# led2001-buck-flashlight-driver-17mm-mk-1.net
KiCad netlist of a schematic drawn in EAGLE
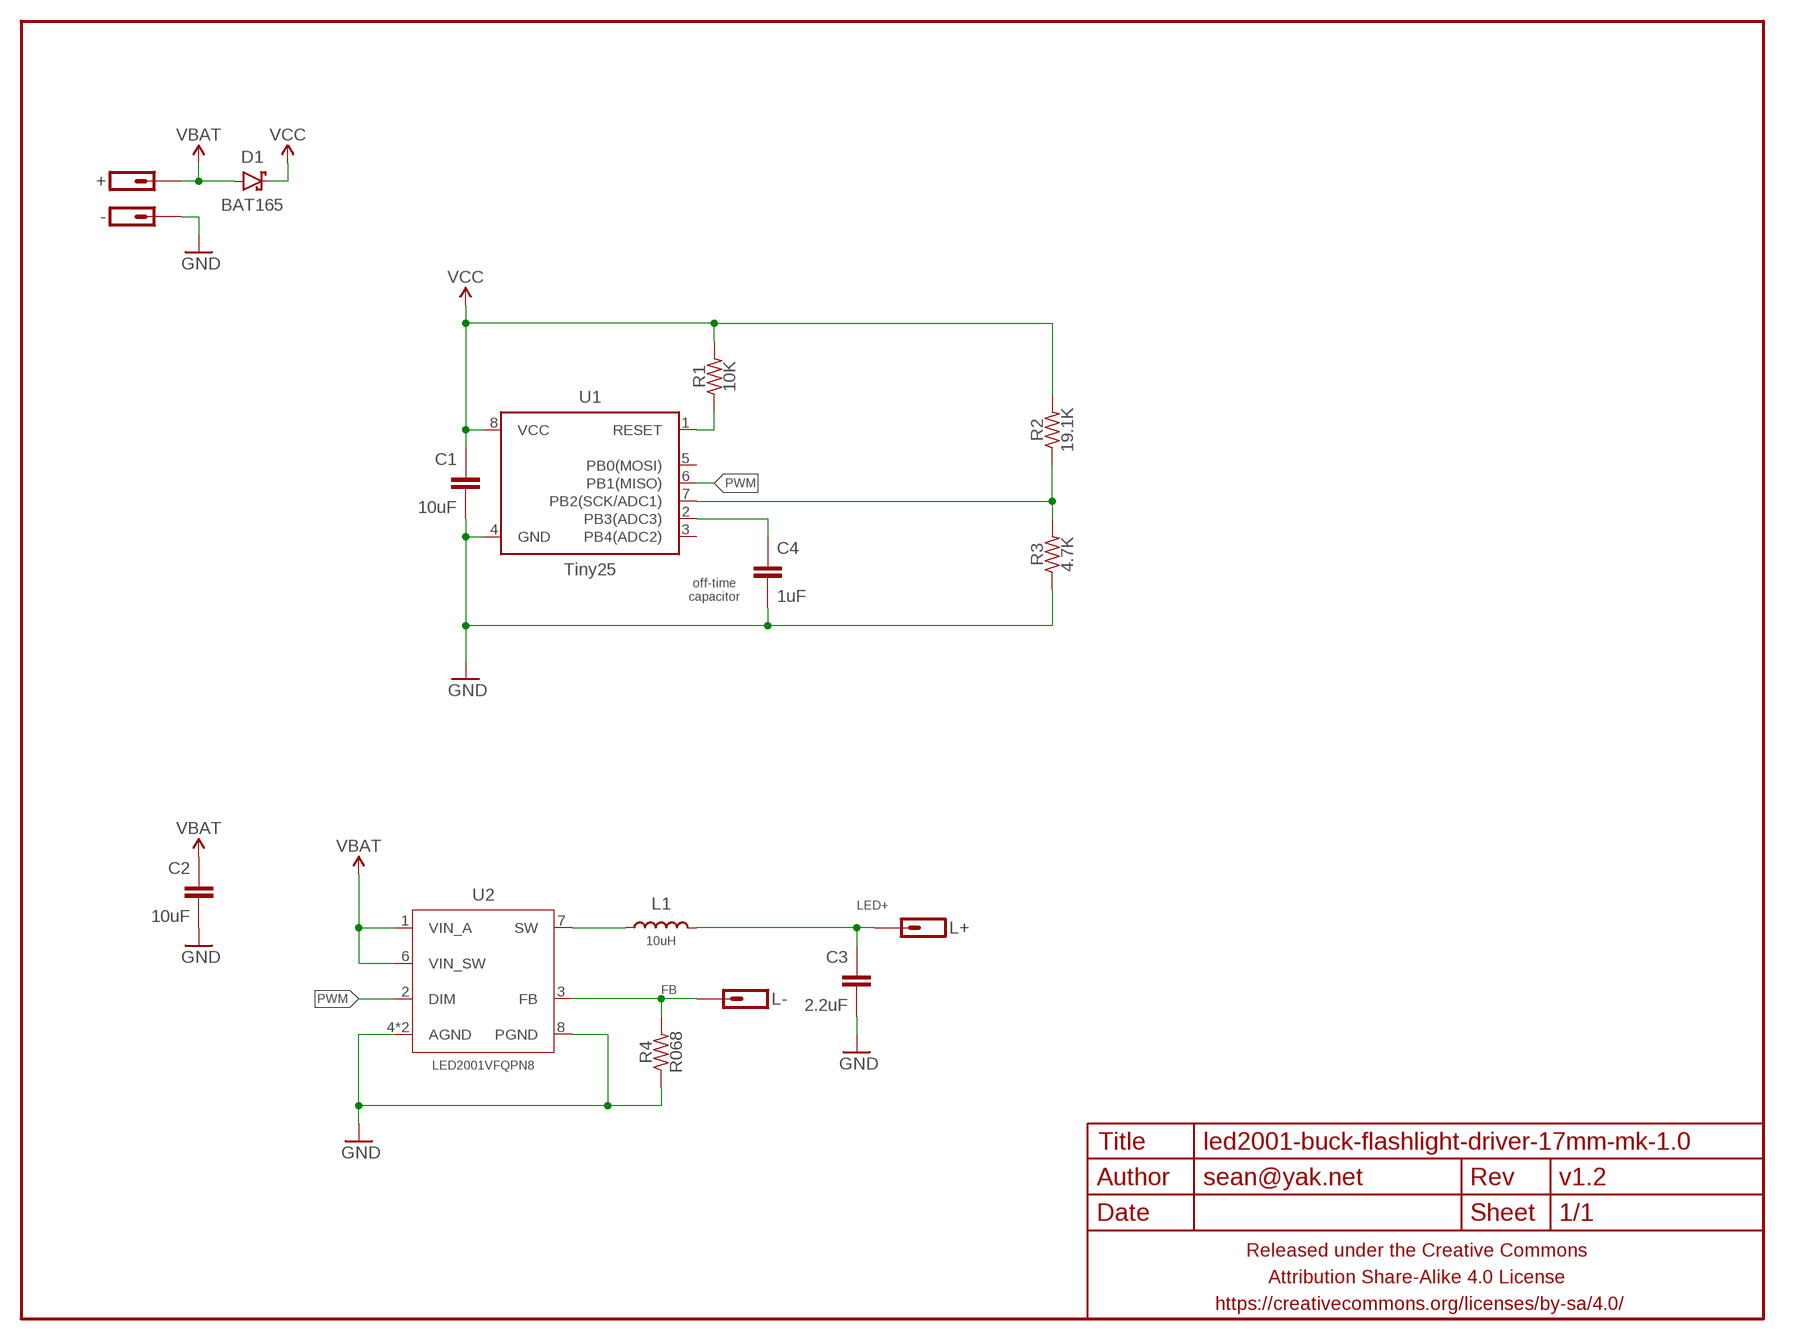
[diagram p0: schematic, sheet 1]

(export (version "E")
  (design (tool "Eeschema 10.0.6"))
  (components
    (comp (ref "+")
      (value "M01PTH-1MM-CIR-NS")
      (footprint "eagle-import:1X01-1MM-CIR-NS")
      (libsource (lib "eagle-import") (part "M01PTH-1MM-CIR-NS"))
    )
    (comp (ref "-")
      (value "M01NOT-A-VIA-NOPE")
      (footprint "eagle-import:1X01_NOSILK_NOSTOP")
      (libsource (lib "eagle-import") (part "M01NOT-A-VIA-NOPE"))
    )
    (comp (ref "C1")
      (value "10uF")
      (footprint "eagle-import:C0603-TIGHTER")
      (libsource (lib "eagle-import") (part "CAPACITOR-CERAMICC0603-TIGHTER"))
    )
    (comp (ref "C2")
      (value "10uF")
      (footprint "eagle-import:C0603-TIGHTER")
      (libsource (lib "eagle-import") (part "CAPACITOR-CERAMICC0603-TIGHTER"))
    )
    (comp (ref "C3")
      (value "2.2uF")
      (footprint "eagle-import:C0603-TIGHTER")
      (libsource (lib "eagle-import") (part "CAPACITOR-CERAMICC0603-TIGHTER"))
    )
    (comp (ref "C4")
      (value "1uF")
      (footprint "eagle-import:C0402")
      (libsource (lib "eagle-import") (part "CAPACITOR-CERAMICC0402"))
    )
    (comp (ref "D1")
      (value "BAT165")
      (footprint "eagle-import:SOD323-SCHOTTKY")
      (libsource (lib "eagle-import") (part "DIODE-SCHOTTKYSOD323"))
    )
    (comp (ref "FRAME1")
      (value "FRAME-LETTERNO_PACKAGE")
      (footprint "eagle-import:DUMMY")
      (fields (field (name "DESIGNER") "sean@yak.net") (field (name "VERSION") "v1.2"))
      (libsource (lib "eagle-import") (part "FRAME-LETTERNO_PACKAGE"))
    )
    (comp (ref "L+")
      (value "M01PTH-1MM-CIR-NS")
      (footprint "eagle-import:1X01-1MM-CIR-NS")
      (libsource (lib "eagle-import") (part "M01PTH-1MM-CIR-NS"))
    )
    (comp (ref "L-")
      (value "M01PTH-1MM-CIR-NS")
      (footprint "eagle-import:1X01-1MM-CIR-NS")
      (libsource (lib "eagle-import") (part "M01PTH-1MM-CIR-NS"))
    )
    (comp (ref "L1")
      (value "10uH")
      (footprint "eagle-import:XAL40X0")
      (libsource (lib "eagle-import") (part "INDUCTORXAL40X0"))
    )
    (comp (ref "R1")
      (value "10K")
      (footprint "eagle-import:R0402")
      (libsource (lib "eagle-import") (part "RESISTORR0402"))
    )
    (comp (ref "R2")
      (value "19.1K")
      (footprint "eagle-import:R0603-TIGHTER")
      (libsource (lib "eagle-import") (part "RESISTORR0603-TIGHTER"))
    )
    (comp (ref "R3")
      (value "4.7K")
      (footprint "eagle-import:R0603-TIGHTER")
      (libsource (lib "eagle-import") (part "RESISTORR0603-TIGHTER"))
    )
    (comp (ref "R4")
      (value "R068")
      (footprint "eagle-import:R0805-TIGHTER")
      (libsource (lib "eagle-import") (part "RESISTORR0805-TIGHTER"))
    )
    (comp (ref "U1")
      (value "Tiny25")
      (footprint "eagle-import:SO08-SKINNYPADS")
      (libsource (lib "eagle-import") (part "ATTINY45TINY25-SOICN-NARROWER"))
    )
    (comp (ref "U2")
      (value "LED2001VFQPN8")
      (footprint "eagle-import:VFQFPN8-4X4")
      (libsource (lib "eagle-import") (part "LED2001VFQPN8"))
    )
  )
  (nets
    (net (code "1") (name "/FB") (class "Default")
      (node (ref "L-") (pin "1") (pinfunction "1_1") (pintype "passive"))
      (node (ref "R4") (pin "2") (pinfunction "2_2") (pintype "passive"))
      (node (ref "U2") (pin "3") (pinfunction "FB_3") (pintype "bidirectional"))
    )
    (net (code "2") (name "/LED+") (class "Default")
      (node (ref "C3") (pin "1") (pinfunction "1_1") (pintype "passive"))
      (node (ref "L+") (pin "1") (pinfunction "1_1") (pintype "passive"))
      (node (ref "L1") (pin "P$2") (pinfunction "2_P$2") (pintype "passive"))
    )
    (net (code "3") (name "GND") (class "Default")
      (node (ref "-") (pin "P$1") (pinfunction "1_P$1") (pintype "passive"))
      (node (ref "C1") (pin "2") (pinfunction "2_2") (pintype "passive"))
      (node (ref "C2") (pin "2") (pinfunction "2_2") (pintype "passive"))
      (node (ref "C3") (pin "2") (pinfunction "2_2") (pintype "passive"))
      (node (ref "C4") (pin "2") (pinfunction "2_2") (pintype "passive"))
      (node (ref "R3") (pin "1") (pinfunction "1_1") (pintype "passive"))
      (node (ref "R4") (pin "1") (pinfunction "1_1") (pintype "passive"))
      (node (ref "U1") (pin "4") (pinfunction "GND_4") (pintype "bidirectional"))
      (node (ref "U2") (pin "4") (pinfunction "AGND_4") (pintype "bidirectional"))
      (node (ref "U2") (pin "8") (pinfunction "PGND_8") (pintype "bidirectional"))
      (node (ref "U2") (pin "9") (pinfunction "AGND_9") (pintype "bidirectional"))
    )
    (net (code "4") (name "Net-(L1-1)") (class "Default")
      (node (ref "L1") (pin "P$1") (pinfunction "1_P$1") (pintype "passive"))
      (node (ref "U2") (pin "7") (pinfunction "SW_7") (pintype "bidirectional"))
    )
    (net (code "5") (name "Net-(U1-PB2(SCK{slash}ADC1))") (class "Default")
      (node (ref "R2") (pin "1") (pinfunction "1_1") (pintype "passive"))
      (node (ref "R3") (pin "2") (pinfunction "2_2") (pintype "passive"))
      (node (ref "U1") (pin "7") (pinfunction "PB2(SCK/ADC1)_7") (pintype "bidirectional"))
    )
    (net (code "6") (name "Net-(U1-PB3(ADC3))") (class "Default")
      (node (ref "C4") (pin "1") (pinfunction "1_1") (pintype "passive"))
      (node (ref "U1") (pin "2") (pinfunction "PB3(ADC3)_2") (pintype "bidirectional"))
    )
    (net (code "7") (name "Net-(U1-RESET)") (class "Default")
      (node (ref "R1") (pin "1") (pinfunction "1_1") (pintype "passive"))
      (node (ref "U1") (pin "1") (pinfunction "RESET_1") (pintype "bidirectional"))
    )
    (net (code "8") (name "PWM") (class "Default")
      (node (ref "U1") (pin "6") (pinfunction "PB1(MISO)_6") (pintype "bidirectional"))
      (node (ref "U2") (pin "2") (pinfunction "DIM_2") (pintype "bidirectional"))
    )
    (net (code "9") (name "VBAT") (class "Default")
      (node (ref "+") (pin "1") (pinfunction "1_1") (pintype "passive"))
      (node (ref "C2") (pin "1") (pinfunction "1_1") (pintype "passive"))
      (node (ref "D1") (pin "A") (pinfunction "A_A") (pintype "passive"))
      (node (ref "U2") (pin "1") (pinfunction "VIN_A_1") (pintype "bidirectional"))
      (node (ref "U2") (pin "6") (pinfunction "VIN_SW_6") (pintype "bidirectional"))
    )
    (net (code "10") (name "VCC") (class "Default")
      (node (ref "C1") (pin "1") (pinfunction "1_1") (pintype "passive"))
      (node (ref "D1") (pin "C") (pinfunction "C_C") (pintype "passive"))
      (node (ref "R1") (pin "2") (pinfunction "2_2") (pintype "passive"))
      (node (ref "R2") (pin "2") (pinfunction "2_2") (pintype "passive"))
      (node (ref "U1") (pin "8") (pinfunction "VCC_8") (pintype "bidirectional"))
    )
    (net (code "11") (name "unconnected-(U1-PB0(MOSI)-Pad5)") (class "Default")
      (node (ref "U1") (pin "5") (pinfunction "PB0(MOSI)_5") (pintype "bidirectional"))
    )
    (net (code "12") (name "unconnected-(U1-PB4(ADC2)-Pad3)") (class "Default")
      (node (ref "U1") (pin "3") (pinfunction "PB4(ADC2)_3") (pintype "bidirectional"))
    )
  )
)
